# 555-schematic.net
KiCad netlist of a schematic drawn in Altium Designer
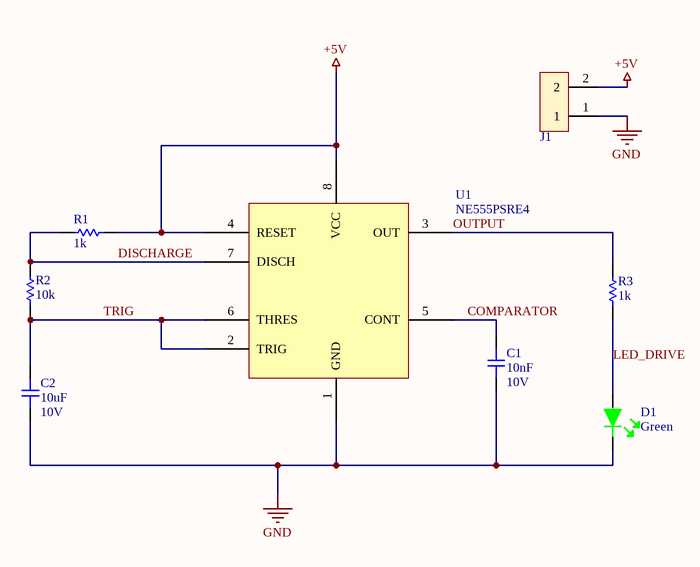
[diagram p0: 555-schematic.SchDoc]

(export (version "E")
  (design (tool "Eeschema 10.0.6"))
  (components
    (comp (ref "C1")
      (value "10nF")
      (footprint "C603")
      (description "Cap Ceramic 0.01uF 10V X7R 10% SMD 0603 125C Paper T/R")
      (fields
        (field (name "MANUFACTURER") "Yageo")
        (field (name "MANUFACTURER PART NUMBER") "CC0603KRX7R6BB103")
        (field (name "VOLTAGE RATING (DC)") "10V")
      )
      (libsource (lib "Schlib1") (part "CC0603KRX7R6BB103"))
    )
    (comp (ref "C2")
      (value "10uF")
      (footprint "C603")
      (description "CAPACITOR, 0805, X6S, 10V, 10UF")
      (fields
        (field (name "MANUFACTURER") "Murata")
        (field (name "MANUFACTURER PART NUMBER") "GRM21BC81A106KE18L")
        (field (name "VOLTAGE") "10V")
      )
      (libsource (lib "Schlib1") (part "GRM21BC81A106KE18L"))
    )
    (comp (ref "D1")
      (value "Green")
      (footprint "LED_0603")
      (description "Green 0805 130 º Min 5 mcd Typical 12 mcd Water Clear Lens SMT LED")
      (fields
        (field (name "MANUFACTURER") "Vishay Lite-On")
        (field (name "MANUFACTURER PART NUMBER") "LTST-C171GKT")
      )
      (libsource (lib "Schlib1") (part "LTST-C171GKT"))
    )
    (comp (ref "J1")
      (value "PREC002SAAN-RC")
      (footprint "2CON")
      (description "CONN HEADER VERT 2POS 2.54MM")
      (fields (field (name "MANUFACTURER") "Sullins"))
      (libsource (lib "Schlib1") (part "PREC002SAAN-RC"))
    )
    (comp (ref "R1")
      (value "1k")
      (footprint "R0603")
      (fields
        (field (name "MANUFACTURER") "Rohm")
        (field (name "MANUFACTURER PART NUMBER") "ESR03EZPJ102")
        (field (name "TOLERANCE") "5%")
      )
      (libsource (lib "Schlib1") (part "ESR03EZPJ102"))
    )
    (comp (ref "R2")
      (value "10k")
      (footprint "R0603")
      (description "Res Thick Film 0603 10K Ohm 5% 1/10W ±100ppm/°C Molded SMD SMD Paper T/R")
      (fields
        (field (name "MANUFACTURER") "Stackpole Electronics")
        (field (name "MANUFACTURER PART NUMBER") "RMCF0603JT10K0")
      )
      (libsource (lib "Schlib1") (part "RMCF0603JT10K0"))
    )
    (comp (ref "R3")
      (value "1k")
      (footprint "R0603")
      (fields
        (field (name "MANUFACTURER") "Rohm")
        (field (name "MANUFACTURER PART NUMBER") "ESR03EZPJ102")
        (field (name "TOLERANCE") "5%")
      )
      (libsource (lib "Schlib1") (part "ESR03EZPJ102"))
    )
    (comp (ref "U1")
      (value "NE555PSRE4")
      (footprint "SOIC-8")
      (description "IC OSC SINGLE TIMER 100KHZ 8SO")
      (fields (field (name "MANUFACTURER") "Texas Instruments"))
      (libsource (lib "Schlib1") (part "NE555PSRE4"))
    )
  )
  (nets
    (net (code "1") (name "+5V") (class "Default")
      (node (ref "J1") (pin "2") (pinfunction "2_2") (pintype "passive"))
      (node (ref "R1") (pin "1") (pinfunction "1_1") (pintype "passive"))
      (node (ref "U1") (pin "4") (pinfunction "RESET_4") (pintype "passive"))
      (node (ref "U1") (pin "8") (pinfunction "VCC_8") (pintype "passive"))
    )
    (net (code "2") (name "/COMPARATOR") (class "Default")
      (node (ref "C1") (pin "2") (pinfunction "2_2") (pintype "passive"))
      (node (ref "U1") (pin "5") (pinfunction "CONT_5") (pintype "passive"))
    )
    (net (code "3") (name "/DISCHARGE") (class "Default")
      (node (ref "R1") (pin "2") (pinfunction "2_2") (pintype "passive"))
      (node (ref "R2") (pin "2") (pinfunction "2_2") (pintype "passive"))
      (node (ref "U1") (pin "7") (pinfunction "DISCH_7") (pintype "passive"))
    )
    (net (code "4") (name "/LED_DRIVE") (class "Default")
      (node (ref "D1") (pin "1") (pinfunction "1_1") (pintype "passive"))
      (node (ref "R3") (pin "1") (pinfunction "1_1") (pintype "passive"))
    )
    (net (code "5") (name "/OUTPUT") (class "Default")
      (node (ref "R3") (pin "2") (pinfunction "2_2") (pintype "passive"))
      (node (ref "U1") (pin "3") (pinfunction "OUT_3") (pintype "passive"))
    )
    (net (code "6") (name "/TRIG") (class "Default")
      (node (ref "C2") (pin "2") (pinfunction "2_2") (pintype "passive"))
      (node (ref "R2") (pin "1") (pinfunction "1_1") (pintype "passive"))
      (node (ref "U1") (pin "2") (pinfunction "TRIG_2") (pintype "passive"))
      (node (ref "U1") (pin "6") (pinfunction "THRES_6") (pintype "passive"))
    )
    (net (code "7") (name "GND") (class "Default")
      (node (ref "C1") (pin "1") (pinfunction "1_1") (pintype "passive"))
      (node (ref "C2") (pin "1") (pinfunction "1_1") (pintype "passive"))
      (node (ref "D1") (pin "2") (pinfunction "2_2") (pintype "passive"))
      (node (ref "J1") (pin "1") (pinfunction "1_1") (pintype "passive"))
      (node (ref "U1") (pin "1") (pinfunction "GND_1") (pintype "passive"))
    )
  )
)
